# wch554e.net
KiCad netlist of a schematic drawn in Altium Designer
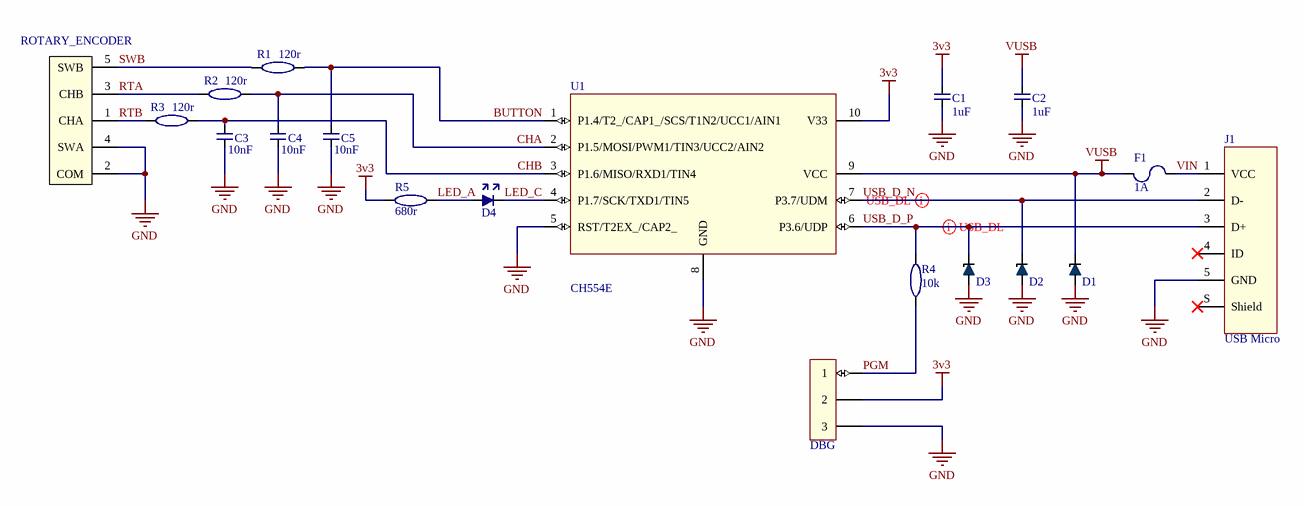
[diagram p0: wch554e.SchDoc]

(export (version "E")
  (design (tool "Eeschema 10.0.6"))
  (components
    (comp (ref "C1")
      (value "1uF")
      (footprint "MLCC_0603")
      (description "MLCC")
      (libsource (lib "wch554e") (part "CAP_CERAMIC"))
    )
    (comp (ref "C2")
      (value "1uF")
      (footprint "MLCC_0603")
      (description "MLCC")
      (libsource (lib "wch554e") (part "CAP_CERAMIC"))
    )
    (comp (ref "C3")
      (value "10nF")
      (footprint "MLCC_0603")
      (description "MLCC")
      (libsource (lib "wch554e") (part "CAP_CERAMIC"))
    )
    (comp (ref "C4")
      (value "10nF")
      (footprint "MLCC_0603")
      (description "MLCC")
      (libsource (lib "wch554e") (part "CAP_CERAMIC"))
    )
    (comp (ref "C5")
      (value "10nF")
      (footprint "MLCC_0603")
      (description "MLCC")
      (libsource (lib "wch554e") (part "CAP_CERAMIC"))
    )
    (comp (ref "D1")
      (value "TVS_DIODE")
      (footprint "TVS_DIODE")
      (description "TVS Diode")
      (libsource (lib "wch554e") (part "TVS_DIODE"))
    )
    (comp (ref "D2")
      (value "TVS_DIODE")
      (footprint "TVS_DIODE")
      (description "TVS Diode")
      (libsource (lib "wch554e") (part "TVS_DIODE"))
    )
    (comp (ref "D3")
      (value "TVS_DIODE")
      (footprint "TVS_DIODE")
      (description "TVS Diode")
      (libsource (lib "wch554e") (part "TVS_DIODE"))
    )
    (comp (ref "D4")
      (value "~")
      (footprint "SMT_LED_0603")
      (description "LED")
      (libsource (lib "wch554e") (part "LED"))
    )
    (comp (ref "DBG")
      (value "CON4")
      (footprint "CON4")
      (description "Debug header")
      (libsource (lib "wch554e") (part "CON4"))
    )
    (comp (ref "F1")
      (value "1A")
      (footprint "FUSE_0805")
      (description "FUSE")
      (libsource (lib "wch554e") (part "FUSE"))
    )
    (comp (ref "J1")
      (value "USB Micro")
      (footprint "USB MICRO B")
      (description "USB Receptacle")
      (libsource (lib "wch554e") (part "USB_SOCKET"))
    )
    (comp (ref "R1")
      (value "120r")
      (footprint "SMT_RES_0603")
      (description "Resistor")
      (libsource (lib "wch554e") (part "RESISTOR"))
    )
    (comp (ref "R2")
      (value "120r")
      (footprint "SMT_RES_0603")
      (description "Resistor")
      (libsource (lib "wch554e") (part "RESISTOR"))
    )
    (comp (ref "R3")
      (value "120r")
      (footprint "SMT_RES_0603")
      (description "Resistor")
      (libsource (lib "wch554e") (part "RESISTOR"))
    )
    (comp (ref "R4")
      (value "10k")
      (footprint "SMT_RES_0603")
      (description "Resistor")
      (libsource (lib "") (part "RESISTOR_1"))
    )
    (comp (ref "R5")
      (value "680r")
      (footprint "SMT_RES_0603")
      (description "Resistor")
      (libsource (lib "wch554e") (part "RESISTOR"))
    )
    (comp (ref "ROTARY_ENCODER")
      (value "ROTARY_ENCODER")
      (footprint "ENCODER")
      (description "Rotary Encoder")
      (libsource (lib "wch554e") (part "ROTARY_ENCODER"))
    )
    (comp (ref "U1") (value "CH554E") (footprint "MSOP10") (libsource (lib "wch554e") (part "CH554E")))
  )
  (nets
    (net (code "1") (name "/BUTTON") (class "Default")
      (node (ref "C5") (pin "2") (pinfunction "B_2") (pintype "passive"))
      (node (ref "R1") (pin "2") (pinfunction "B_2") (pintype "passive"))
      (node (ref "U1") (pin "1") (pinfunction "P1.4/T2_/CAP1_/SCS/T1N2/UCC1/AIN1_1") (pintype "bidirectional"))
    )
    (net (code "2") (name "/CHA") (class "Default")
      (node (ref "C4") (pin "2") (pinfunction "B_2") (pintype "passive"))
      (node (ref "R2") (pin "2") (pinfunction "B_2") (pintype "passive"))
      (node (ref "U1") (pin "2") (pinfunction "P1.5/MOSI/PWM1/TIN3/UCC2/AIN2_2") (pintype "bidirectional"))
    )
    (net (code "3") (name "/CHB") (class "Default")
      (node (ref "C3") (pin "2") (pinfunction "B_2") (pintype "passive"))
      (node (ref "R3") (pin "2") (pinfunction "B_2") (pintype "passive"))
      (node (ref "U1") (pin "3") (pinfunction "P1.6/MISO/RXD1/TIN4_3") (pintype "bidirectional"))
    )
    (net (code "4") (name "/LED_A") (class "Default")
      (node (ref "D4") (pin "1") (pinfunction "CATHODE_1") (pintype "passive"))
      (node (ref "R5") (pin "2") (pinfunction "B_2") (pintype "passive"))
    )
    (net (code "5") (name "/LED_C") (class "Default")
      (node (ref "D4") (pin "2") (pinfunction "ANODE_2") (pintype "passive"))
      (node (ref "U1") (pin "4") (pinfunction "P1.7/SCK/TXD1/TIN5_4") (pintype "bidirectional"))
    )
    (net (code "6") (name "/PGM") (class "Default")
      (node (ref "DBG") (pin "1") (pinfunction "1_1") (pintype "bidirectional"))
      (node (ref "R4") (pin "1") (pinfunction "A_1") (pintype "passive"))
    )
    (net (code "7") (name "/RTA") (class "Default")
      (node (ref "R2") (pin "1") (pinfunction "A_1") (pintype "passive"))
      (node (ref "ROTARY_ENCODER") (pin "3") (pinfunction "CHB_3") (pintype "passive"))
    )
    (net (code "8") (name "/RTB") (class "Default")
      (node (ref "R3") (pin "1") (pinfunction "A_1") (pintype "passive"))
      (node (ref "ROTARY_ENCODER") (pin "1") (pinfunction "CHA_1") (pintype "passive"))
    )
    (net (code "9") (name "/SWB") (class "Default")
      (node (ref "R1") (pin "1") (pinfunction "A_1") (pintype "passive"))
      (node (ref "ROTARY_ENCODER") (pin "5") (pinfunction "SWB_5") (pintype "passive"))
    )
    (net (code "10") (name "/USB_D_N") (class "Default")
      (node (ref "D2") (pin "1") (pinfunction "K_1") (pintype "passive"))
      (node (ref "J1") (pin "2") (pinfunction "D-_2") (pintype "passive"))
      (node (ref "U1") (pin "7") (pinfunction "P3.7/UDM_7") (pintype "bidirectional"))
    )
    (net (code "11") (name "/USB_D_P") (class "Default")
      (node (ref "D3") (pin "1") (pinfunction "K_1") (pintype "passive"))
      (node (ref "J1") (pin "3") (pinfunction "D+_3") (pintype "passive"))
      (node (ref "R4") (pin "2") (pinfunction "B_2") (pintype "passive"))
      (node (ref "U1") (pin "6") (pinfunction "P3.6/UDP_6") (pintype "bidirectional"))
    )
    (net (code "12") (name "/VIN") (class "Default")
      (node (ref "F1") (pin "1") (pinfunction "1_1") (pintype "power_in"))
      (node (ref "J1") (pin "1") (pinfunction "VCC_1") (pintype "passive"))
    )
    (net (code "13") (name "3v3") (class "Default")
      (node (ref "C1") (pin "2") (pinfunction "B_2") (pintype "passive"))
      (node (ref "DBG") (pin "2") (pinfunction "2_2") (pintype "power_in"))
      (node (ref "R5") (pin "1") (pinfunction "A_1") (pintype "passive"))
      (node (ref "U1") (pin "10") (pinfunction "V33_10") (pintype "power_in"))
    )
    (net (code "14") (name "GND") (class "Default")
      (node (ref "C1") (pin "1") (pinfunction "A_1") (pintype "passive"))
      (node (ref "C2") (pin "1") (pinfunction "A_1") (pintype "passive"))
      (node (ref "C3") (pin "1") (pinfunction "A_1") (pintype "passive"))
      (node (ref "C4") (pin "1") (pinfunction "A_1") (pintype "passive"))
      (node (ref "C5") (pin "1") (pinfunction "A_1") (pintype "passive"))
      (node (ref "D1") (pin "2") (pinfunction "A_2") (pintype "passive"))
      (node (ref "D2") (pin "2") (pinfunction "A_2") (pintype "passive"))
      (node (ref "D3") (pin "2") (pinfunction "A_2") (pintype "passive"))
      (node (ref "DBG") (pin "3") (pinfunction "3_3") (pintype "power_in"))
      (node (ref "J1") (pin "5") (pinfunction "GND_5") (pintype "passive"))
      (node (ref "ROTARY_ENCODER") (pin "2") (pinfunction "COM_2") (pintype "passive"))
      (node (ref "ROTARY_ENCODER") (pin "4") (pinfunction "SWA_4") (pintype "passive"))
      (node (ref "U1") (pin "5") (pinfunction "RST/T2EX_/CAP2__5") (pintype "bidirectional"))
      (node (ref "U1") (pin "8") (pinfunction "GND_8") (pintype "power_in"))
    )
    (net (code "15") (name "VUSB") (class "Default")
      (node (ref "C2") (pin "2") (pinfunction "B_2") (pintype "passive"))
      (node (ref "D1") (pin "1") (pinfunction "K_1") (pintype "passive"))
      (node (ref "F1") (pin "2") (pinfunction "2_2") (pintype "power_in"))
      (node (ref "U1") (pin "9") (pinfunction "VCC_9") (pintype "power_in"))
    )
    (net (code "16") (name "unconnected-(J1-ID-Pad4)") (class "Default")
      (node (ref "J1") (pin "4") (pinfunction "ID_4") (pintype "passive+no_connect"))
    )
    (net (code "17") (name "unconnected-(J1-Shield-PadS)") (class "Default")
      (node (ref "J1") (pin "S") (pinfunction "Shield_S") (pintype "passive+no_connect"))
    )
  )
)
